# gain.net
KiCad netlist of a schematic drawn in Altium Designer
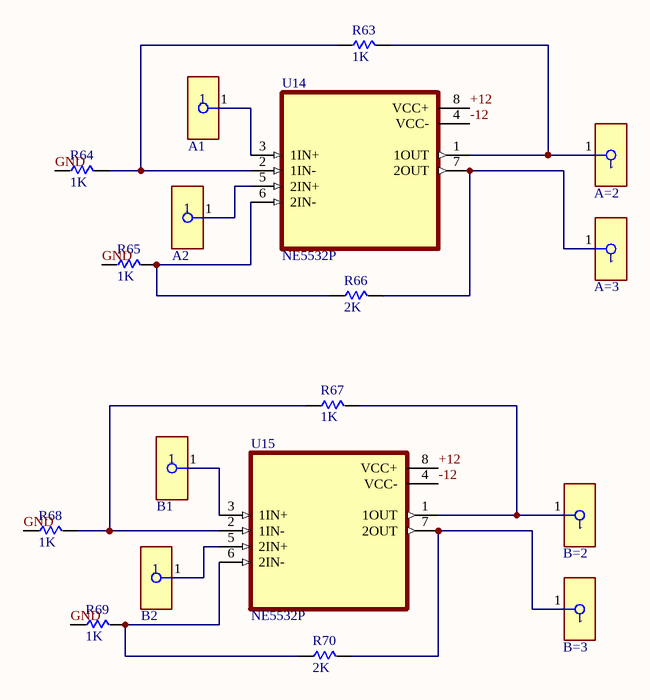
[diagram p0: gain.SchDoc]

(export (version "E")
  (design (tool "Eeschema 10.0.6"))
  (components
    (comp (ref "A1")
      (value "1581-5")
      (footprint "FP-1581-5-MFG")
      (description "CONN BANANA JACK TURRET GREEN")
      (libsource (lib "") (part "CMP-73906-000011-1_1"))
    )
    (comp (ref "A2")
      (value "1581-5")
      (footprint "FP-1581-5-MFG")
      (description "CONN BANANA JACK TURRET GREEN")
      (libsource (lib "") (part "CMP-73906-000011-1_1"))
    )
    (comp (ref "A=2")
      (value "1581-5")
      (footprint "FP-1581-5-MFG")
      (description "CONN BANANA JACK TURRET GREEN")
      (libsource (lib "Schlib1") (part "CMP-73906-000011-1"))
    )
    (comp (ref "A=3")
      (value "1581-5")
      (footprint "FP-1581-5-MFG")
      (description "CONN BANANA JACK TURRET GREEN")
      (libsource (lib "Schlib1") (part "CMP-73906-000011-1"))
    )
    (comp (ref "B1")
      (value "1581-5")
      (footprint "FP-1581-5-MFG")
      (description "CONN BANANA JACK TURRET GREEN")
      (libsource (lib "") (part "CMP-73906-000011-1_1"))
    )
    (comp (ref "B2")
      (value "1581-5")
      (footprint "FP-1581-5-MFG")
      (description "CONN BANANA JACK TURRET GREEN")
      (libsource (lib "") (part "CMP-73906-000011-1_1"))
    )
    (comp (ref "B=2")
      (value "1581-5")
      (footprint "FP-1581-5-MFG")
      (description "CONN BANANA JACK TURRET GREEN")
      (libsource (lib "Schlib1") (part "CMP-73906-000011-1"))
    )
    (comp (ref "B=3")
      (value "1581-5")
      (footprint "FP-1581-5-MFG")
      (description "CONN BANANA JACK TURRET GREEN")
      (libsource (lib "Schlib1") (part "CMP-73906-000011-1"))
    )
    (comp (ref "R63")
      (value "1K")
      (footprint "RESAD1100W55L680D260")
      (description "1.07 kOhms Â±1% 0.25W, 1/4W Through Hole Resistor Axial - Metal Film")
      (fields (field (name "MF") "Yageo") (field (name "MP") "MFR-25FBF52-1K"))
      (libsource (lib "Schlib1") (part "MFR-25FBF52-1K"))
    )
    (comp (ref "R64")
      (value "1K")
      (footprint "RESAD1100W55L680D260")
      (description "1.07 kOhms Â±1% 0.25W, 1/4W Through Hole Resistor Axial - Metal Film")
      (fields (field (name "MF") "Yageo") (field (name "MP") "MFR-25FBF52-1K"))
      (libsource (lib "Schlib1") (part "MFR-25FBF52-1K"))
    )
    (comp (ref "R65")
      (value "1K")
      (footprint "RESAD1100W55L680D260")
      (description "1.07 kOhms Â±1% 0.25W, 1/4W Through Hole Resistor Axial - Metal Film")
      (fields (field (name "MF") "Yageo") (field (name "MP") "MFR-25FBF52-1K"))
      (libsource (lib "Schlib1") (part "MFR-25FBF52-1K"))
    )
    (comp (ref "R66")
      (value "2K")
      (footprint "RESAD1100W55L680D260")
      (description "1.07 kOhms Â±1% 0.25W, 1/4W Through Hole Resistor Axial - Metal Film")
      (fields (field (name "MF") "Yageo") (field (name "MP") "MFR-25FBF52-1K"))
      (libsource (lib "Schlib1") (part "MFR-25FBF52-1K"))
    )
    (comp (ref "R67")
      (value "1K")
      (footprint "RESAD1100W55L680D260")
      (description "1.07 kOhms Â±1% 0.25W, 1/4W Through Hole Resistor Axial - Metal Film")
      (fields (field (name "MF") "Yageo") (field (name "MP") "MFR-25FBF52-1K"))
      (libsource (lib "Schlib1") (part "MFR-25FBF52-1K"))
    )
    (comp (ref "R68")
      (value "1K")
      (footprint "RESAD1100W55L680D260")
      (description "1.07 kOhms Â±1% 0.25W, 1/4W Through Hole Resistor Axial - Metal Film")
      (fields (field (name "MF") "Yageo") (field (name "MP") "MFR-25FBF52-1K"))
      (libsource (lib "Schlib1") (part "MFR-25FBF52-1K"))
    )
    (comp (ref "R69")
      (value "1K")
      (footprint "RESAD1100W55L680D260")
      (description "1.07 kOhms Â±1% 0.25W, 1/4W Through Hole Resistor Axial - Metal Film")
      (fields (field (name "MF") "Yageo") (field (name "MP") "MFR-25FBF52-1K"))
      (libsource (lib "Schlib1") (part "MFR-25FBF52-1K"))
    )
    (comp (ref "R70")
      (value "2K")
      (footprint "RESAD1100W55L680D260")
      (description "1.07 kOhms Â±1% 0.25W, 1/4W Through Hole Resistor Axial - Metal Film")
      (fields (field (name "MF") "Yageo") (field (name "MP") "MFR-25FBF52-1K"))
      (libsource (lib "Schlib1") (part "MFR-25FBF52-1K"))
    )
    (comp (ref "U14")
      (value "NE5532P")
      (footprint "DIP794W45P254L959H508Q8")
      (description "Dual, 30-V, 10-MHz, low-noise operational amplifier for audio applications")
      (fields (field (name "MF") "Texas Instruments"))
      (libsource (lib "Schlib1") (part "NE5532P"))
    )
    (comp (ref "U15")
      (value "NE5532P")
      (footprint "DIP794W45P254L959H508Q8")
      (description "Dual, 30-V, 10-MHz, low-noise operational amplifier for audio applications")
      (fields (field (name "MF") "Texas Instruments"))
      (libsource (lib "Schlib1") (part "NE5532P"))
    )
  )
  (nets
    (net (code "1") (name "/+12") (class "Default")
      (node (ref "U14") (pin "8") (pinfunction "VCC+_8") (pintype "power_in"))
      (node (ref "U15") (pin "8") (pinfunction "VCC+_8") (pintype "power_in"))
    )
    (net (code "2") (name "/-12") (class "Default")
      (node (ref "U14") (pin "4") (pinfunction "VCC-_4") (pintype "power_in"))
      (node (ref "U15") (pin "4") (pinfunction "VCC-_4") (pintype "power_in"))
    )
    (net (code "3") (name "/GND") (class "Default")
      (node (ref "R64") (pin "1") (pinfunction "1_1") (pintype "passive"))
      (node (ref "R65") (pin "1") (pinfunction "1_1") (pintype "passive"))
      (node (ref "R68") (pin "1") (pinfunction "1_1") (pintype "passive"))
      (node (ref "R69") (pin "1") (pinfunction "1_1") (pintype "passive"))
    )
    (net (code "4") (name "Net-(U14-1IN+)") (class "Default")
      (node (ref "A1") (pin "1") (pinfunction "1_1") (pintype "passive"))
      (node (ref "U14") (pin "3") (pinfunction "1IN+_3") (pintype "input"))
    )
    (net (code "5") (name "Net-(U14-1IN-)") (class "Default")
      (node (ref "R63") (pin "1") (pinfunction "1_1") (pintype "passive"))
      (node (ref "R64") (pin "2") (pinfunction "2_2") (pintype "passive"))
      (node (ref "U14") (pin "2") (pinfunction "1IN-_2") (pintype "input"))
    )
    (net (code "6") (name "Net-(U14-1OUT)") (class "Default")
      (node (ref "A=2") (pin "1") (pinfunction "1_1") (pintype "passive"))
      (node (ref "R63") (pin "2") (pinfunction "2_2") (pintype "passive"))
      (node (ref "U14") (pin "1") (pinfunction "1OUT_1") (pintype "output"))
    )
    (net (code "7") (name "Net-(U14-2IN+)") (class "Default")
      (node (ref "A2") (pin "1") (pinfunction "1_1") (pintype "passive"))
      (node (ref "U14") (pin "5") (pinfunction "2IN+_5") (pintype "input"))
    )
    (net (code "8") (name "Net-(U14-2IN-)") (class "Default")
      (node (ref "R65") (pin "2") (pinfunction "2_2") (pintype "passive"))
      (node (ref "R66") (pin "1") (pinfunction "1_1") (pintype "passive"))
      (node (ref "U14") (pin "6") (pinfunction "2IN-_6") (pintype "input"))
    )
    (net (code "9") (name "Net-(U14-2OUT)") (class "Default")
      (node (ref "A=3") (pin "1") (pinfunction "1_1") (pintype "passive"))
      (node (ref "R66") (pin "2") (pinfunction "2_2") (pintype "passive"))
      (node (ref "U14") (pin "7") (pinfunction "2OUT_7") (pintype "output"))
    )
    (net (code "10") (name "Net-(U15-1IN+)") (class "Default")
      (node (ref "B1") (pin "1") (pinfunction "1_1") (pintype "passive"))
      (node (ref "U15") (pin "3") (pinfunction "1IN+_3") (pintype "input"))
    )
    (net (code "11") (name "Net-(U15-1IN-)") (class "Default")
      (node (ref "R67") (pin "1") (pinfunction "1_1") (pintype "passive"))
      (node (ref "R68") (pin "2") (pinfunction "2_2") (pintype "passive"))
      (node (ref "U15") (pin "2") (pinfunction "1IN-_2") (pintype "input"))
    )
    (net (code "12") (name "Net-(U15-1OUT)") (class "Default")
      (node (ref "B=2") (pin "1") (pinfunction "1_1") (pintype "passive"))
      (node (ref "R67") (pin "2") (pinfunction "2_2") (pintype "passive"))
      (node (ref "U15") (pin "1") (pinfunction "1OUT_1") (pintype "output"))
    )
    (net (code "13") (name "Net-(U15-2IN+)") (class "Default")
      (node (ref "B2") (pin "1") (pinfunction "1_1") (pintype "passive"))
      (node (ref "U15") (pin "5") (pinfunction "2IN+_5") (pintype "input"))
    )
    (net (code "14") (name "Net-(U15-2IN-)") (class "Default")
      (node (ref "R69") (pin "2") (pinfunction "2_2") (pintype "passive"))
      (node (ref "R70") (pin "1") (pinfunction "1_1") (pintype "passive"))
      (node (ref "U15") (pin "6") (pinfunction "2IN-_6") (pintype "input"))
    )
    (net (code "15") (name "Net-(U15-2OUT)") (class "Default")
      (node (ref "B=3") (pin "1") (pinfunction "1_1") (pintype "passive"))
      (node (ref "R70") (pin "2") (pinfunction "2_2") (pintype "passive"))
      (node (ref "U15") (pin "7") (pinfunction "2OUT_7") (pintype "output"))
    )
  )
)
